# 555.net
KiCad netlist of a schematic drawn in EAGLE
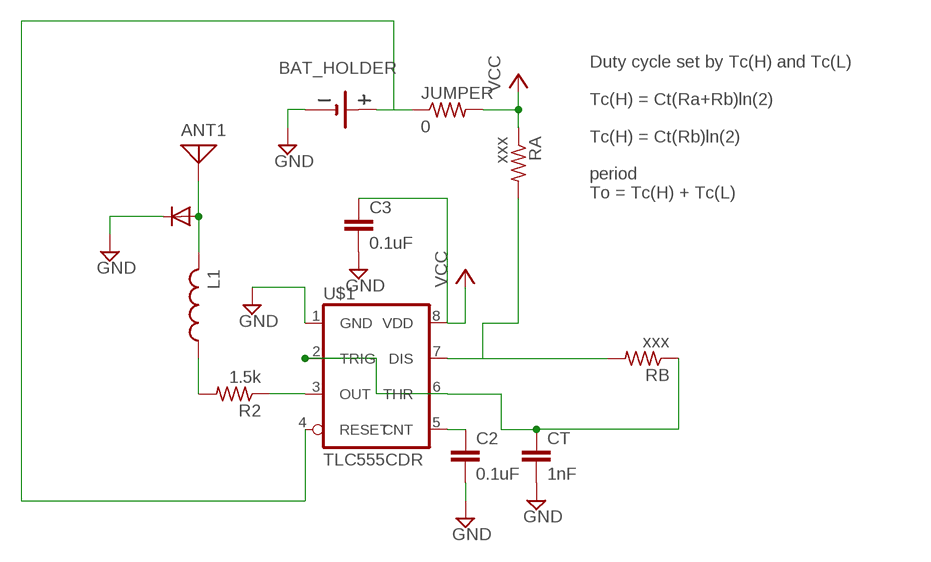
[diagram p0: schematic, sheet 1]

(export (version "E")
  (design (tool "Eeschema 10.0.6"))
  (components
    (comp (ref "ANT1")
      (value "ANTENNA")
      (footprint "eagle-import:PAD-01")
      (libsource (lib "eagle-import") (part "ANTENNA"))
    )
    (comp (ref "C2")
      (value "0.1uF")
      (footprint "eagle-import:C050-024X044")
      (libsource (lib "eagle-import") (part "C-EU050-024X044"))
    )
    (comp (ref "C3")
      (value "0.1uF")
      (footprint "eagle-import:C050-024X044")
      (libsource (lib "eagle-import") (part "C-EU050-024X044"))
    )
    (comp (ref "CT")
      (value "1nF")
      (footprint "eagle-import:C050-024X044")
      (libsource (lib "eagle-import") (part "C-EU050-024X044"))
    )
    (comp (ref "JUMPER")
      (value "0")
      (footprint "eagle-import:M1206")
      (libsource (lib "eagle-import") (part "R-US_M1206"))
    )
    (comp (ref "L1")
      (value "L-USL2012C")
      (footprint "eagle-import:L2012C")
      (libsource (lib "eagle-import") (part "L-USL2012C"))
    )
    (comp (ref "R2")
      (value "1.5k")
      (footprint "eagle-import:M1206")
      (libsource (lib "eagle-import") (part "R-US_M1206"))
    )
    (comp (ref "RA")
      (value "xxx")
      (footprint "eagle-import:M1206")
      (libsource (lib "eagle-import") (part "R-US_M1206"))
    )
    (comp (ref "RB")
      (value "xxx")
      (footprint "eagle-import:M1206")
      (libsource (lib "eagle-import") (part "R-US_M1206"))
    )
    (comp (ref "U$1")
      (value "TLC555CDR")
      (footprint "eagle-import:TLC555CRD")
      (libsource (lib "eagle-import") (part "TLC555CDR"))
    )
    (comp (ref "U$2")
      (value "BAT_HOLDER")
      (footprint "eagle-import:BAT_HOLDER")
      (libsource (lib "eagle-import") (part "BAT_HOLDER"))
    )
    (comp (ref "U$3")
      (value "BAT-15-03W")
      (footprint "eagle-import:BAT-15-03W")
      (libsource (lib "eagle-import") (part "BAT-15-03W"))
    )
  )
  (nets
    (net (code "1") (name "GND") (class "Default")
      (node (ref "C2") (pin "2") (pinfunction "2_2") (pintype "passive"))
      (node (ref "C3") (pin "2") (pinfunction "2_2") (pintype "passive"))
      (node (ref "CT") (pin "2") (pinfunction "2_2") (pintype "passive"))
      (node (ref "U$1") (pin "1") (pinfunction "GND_1") (pintype "input"))
      (node (ref "U$2") (pin "P_G2") (pinfunction "-_P_G2") (pintype "passive"))
      (node (ref "U$2") (pin "P_G3") (pinfunction "-_P_G3") (pintype "passive"))
      (node (ref "U$2") (pin "P_GND") (pinfunction "-_P_GND") (pintype "passive"))
      (node (ref "U$3") (pin "C") (pinfunction "C_C") (pintype "passive"))
    )
    (net (code "2") (name "Net-(ANT1-Pad1)") (class "Default")
      (node (ref "ANT1") (pin "1") (pinfunction "1_1") (pintype "output"))
      (node (ref "L1") (pin "2") (pinfunction "2_2") (pintype "passive"))
      (node (ref "U$3") (pin "A") (pinfunction "A_A") (pintype "passive"))
    )
    (net (code "3") (name "Net-(L1-Pad1)") (class "Default")
      (node (ref "L1") (pin "1") (pinfunction "1_1") (pintype "passive"))
      (node (ref "R2") (pin "2") (pinfunction "2_2") (pintype "passive"))
    )
    (net (code "4") (name "Net-(U$1-CNT)") (class "Default")
      (node (ref "C2") (pin "1") (pinfunction "1_1") (pintype "passive"))
      (node (ref "U$1") (pin "5") (pinfunction "CNT_5") (pintype "power_in"))
    )
    (net (code "5") (name "Net-(U$1-DIS)") (class "Default")
      (node (ref "RA") (pin "2") (pinfunction "2_2") (pintype "passive"))
      (node (ref "RB") (pin "2") (pinfunction "2_2") (pintype "passive"))
      (node (ref "U$1") (pin "7") (pinfunction "DIS_7") (pintype "input"))
    )
    (net (code "6") (name "Net-(U$1-OUT)") (class "Default")
      (node (ref "R2") (pin "1") (pinfunction "1_1") (pintype "passive"))
      (node (ref "U$1") (pin "3") (pinfunction "OUT_3") (pintype "input"))
    )
    (net (code "7") (name "Net-(U$1-RESET)") (class "Default")
      (node (ref "JUMPER") (pin "1") (pinfunction "1_1") (pintype "passive"))
      (node (ref "U$1") (pin "4") (pinfunction "RESET_4") (pintype "input"))
      (node (ref "U$2") (pin "P_+") (pinfunction "+_P_+") (pintype "passive"))
    )
    (net (code "8") (name "Net-(U$1-THR)") (class "Default")
      (node (ref "CT") (pin "1") (pinfunction "1_1") (pintype "passive"))
      (node (ref "RB") (pin "1") (pinfunction "1_1") (pintype "passive"))
      (node (ref "U$1") (pin "2") (pinfunction "TRIG_2") (pintype "power_in"))
      (node (ref "U$1") (pin "6") (pinfunction "THR_6") (pintype "input"))
    )
    (net (code "9") (name "VCC") (class "Default")
      (node (ref "C3") (pin "1") (pinfunction "1_1") (pintype "passive"))
      (node (ref "JUMPER") (pin "2") (pinfunction "2_2") (pintype "passive"))
      (node (ref "RA") (pin "1") (pinfunction "1_1") (pintype "passive"))
      (node (ref "U$1") (pin "8") (pinfunction "VDD_8") (pintype "output"))
    )
    (net (code "10") (name "unconnected-(U$2-PadNC)") (class "Default")
      (node (ref "U$2") (pin "NC") (pinfunction "NC_NC") (pintype "no_connect"))
    )
  )
)
